# properjack.net
KiCad netlist of a schematic drawn in EAGLE
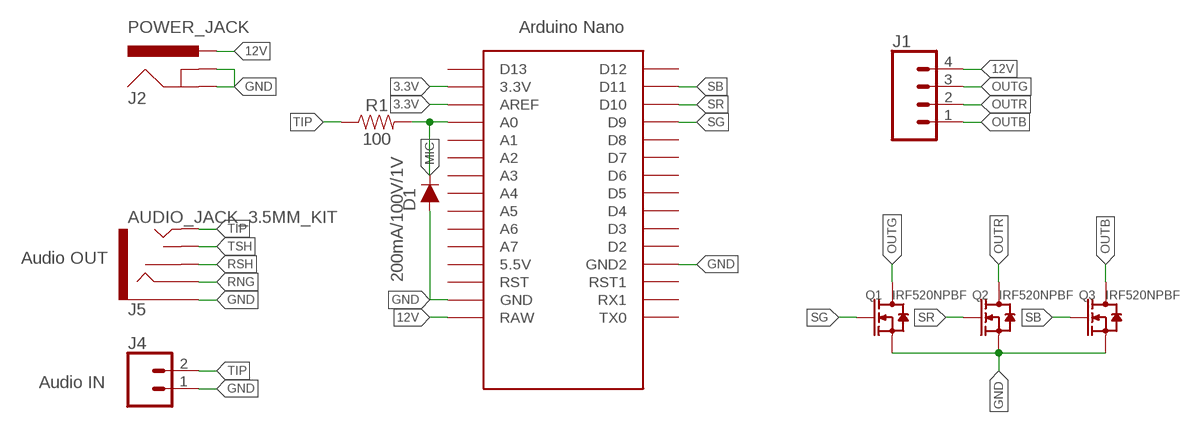
[diagram p0: schematic, sheet 1]

(export (version "E")
  (design (tool "Eeschema 10.0.6"))
  (components
    (comp (ref "D1")
      (value "200mA/100V/1V")
      (footprint "eagle-import:DIODE-1N4148")
      (libsource (lib "eagle-import") (part "DIODE-1N4148"))
    )
    (comp (ref "J1")
      (value "CONN_04LOCK_LONGPADS")
      (footprint "eagle-import:1X04_LOCK_LONGPADS")
      (libsource (lib "eagle-import") (part "CONN_04LOCK_LONGPADS"))
    )
    (comp (ref "J2")
      (value "POWER_JACK")
      (footprint "eagle-import:POWER_JACK_PTH")
      (libsource (lib "eagle-import") (part "POWER_JACK"))
    )
    (comp (ref "J4")
      (value "CONN_02LOCK_LONGPADS")
      (footprint "eagle-import:1X02_LOCK_LONGPADS")
      (libsource (lib "eagle-import") (part "CONN_02LOCK_LONGPADS"))
    )
    (comp (ref "J5")
      (value "AUDIO_JACK_3.5MM_KIT")
      (footprint "eagle-import:AUDIO-JACK-KIT")
      (libsource (lib "eagle-import") (part "AUDIO_JACK_3.5MM_KIT"))
    )
    (comp (ref "Q1")
      (value "IRF520NPBF")
      (footprint "eagle-import:TO-220")
      (libsource (lib "eagle-import") (part "DIP-MOSFET-N-CH-100V-9.7A-IRF520NPBF(TO-220AB)IRL2703"))
    )
    (comp (ref "Q2")
      (value "IRF520NPBF")
      (footprint "eagle-import:TO-220")
      (libsource (lib "eagle-import") (part "DIP-MOSFET-N-CH-100V-9.7A-IRF520NPBF(TO-220AB)IRL2703"))
    )
    (comp (ref "Q3")
      (value "IRF520NPBF")
      (footprint "eagle-import:TO-220")
      (libsource (lib "eagle-import") (part "DIP-MOSFET-N-CH-100V-9.7A-IRF520NPBF(TO-220AB)IRL2703"))
    )
    (comp (ref "R1")
      (value "100")
      (footprint "eagle-import:AXIAL-0.3")
      (libsource (lib "eagle-import") (part "100OHM-HORIZ-1/4W-1%"))
    )
    (comp (ref "U$1")
      (value "NANONOICSP")
      (footprint "eagle-import:NANO_2")
      (libsource (lib "eagle-import") (part "NANONOICSP"))
    )
  )
  (nets
    (net (code "1") (name "3.3V") (class "Default")
      (node (ref "U$1") (pin "3.3V") (pinfunction "3.3V_3.3V") (pintype "bidirectional"))
      (node (ref "U$1") (pin "AREF") (pinfunction "AREF_AREF") (pintype "bidirectional"))
    )
    (net (code "2") (name "12V") (class "Default")
      (node (ref "J1") (pin "4") (pinfunction "4_4") (pintype "passive"))
      (node (ref "J2") (pin "PWR") (pinfunction "PWR_PWR") (pintype "bidirectional"))
      (node (ref "U$1") (pin "RAW") (pinfunction "RAW_RAW") (pintype "bidirectional"))
    )
    (net (code "3") (name "GND") (class "Default")
      (node (ref "D1") (pin "A") (pinfunction "A_A") (pintype "passive"))
      (node (ref "J2") (pin "GND") (pinfunction "GND_GND") (pintype "bidirectional"))
      (node (ref "J2") (pin "GNDBREAK") (pinfunction "GNDBREAK_GNDBREAK") (pintype "bidirectional"))
      (node (ref "J4") (pin "1") (pinfunction "1_1") (pintype "passive"))
      (node (ref "J5") (pin "SLEEVE") (pinfunction "SLEEVE_SLEEVE") (pintype "bidirectional"))
      (node (ref "Q1") (pin "3") (pinfunction "S_3") (pintype "passive"))
      (node (ref "Q2") (pin "3") (pinfunction "S_3") (pintype "passive"))
      (node (ref "Q3") (pin "3") (pinfunction "S_3") (pintype "passive"))
      (node (ref "U$1") (pin "GND") (pinfunction "GND_GND") (pintype "bidirectional"))
      (node (ref "U$1") (pin "GND1") (pinfunction "GND2_GND1") (pintype "bidirectional"))
    )
    (net (code "4") (name "MIC") (class "Default")
      (node (ref "D1") (pin "C") (pinfunction "C_C") (pintype "passive"))
      (node (ref "R1") (pin "P$2") (pinfunction "2_P$2") (pintype "passive"))
      (node (ref "U$1") (pin "A0") (pinfunction "A0_A0") (pintype "bidirectional"))
    )
    (net (code "5") (name "OUTB") (class "Default")
      (node (ref "J1") (pin "1") (pinfunction "1_1") (pintype "passive"))
      (node (ref "Q3") (pin "2") (pinfunction "D_2") (pintype "passive"))
      (node (ref "Q3") (pin "HEAT") (pinfunction "D_HEAT") (pintype "passive"))
    )
    (net (code "6") (name "OUTG") (class "Default")
      (node (ref "J1") (pin "3") (pinfunction "3_3") (pintype "passive"))
      (node (ref "Q1") (pin "2") (pinfunction "D_2") (pintype "passive"))
      (node (ref "Q1") (pin "HEAT") (pinfunction "D_HEAT") (pintype "passive"))
    )
    (net (code "7") (name "OUTR") (class "Default")
      (node (ref "J1") (pin "2") (pinfunction "2_2") (pintype "passive"))
      (node (ref "Q2") (pin "2") (pinfunction "D_2") (pintype "passive"))
      (node (ref "Q2") (pin "HEAT") (pinfunction "D_HEAT") (pintype "passive"))
    )
    (net (code "8") (name "RNG") (class "Default")
      (node (ref "J5") (pin "RING") (pinfunction "RING_RING") (pintype "bidirectional"))
    )
    (net (code "9") (name "RSH") (class "Default")
      (node (ref "J5") (pin "RSH") (pinfunction "RSH_RSH") (pintype "bidirectional"))
    )
    (net (code "10") (name "SB") (class "Default")
      (node (ref "Q3") (pin "1") (pinfunction "G_1") (pintype "passive"))
      (node (ref "U$1") (pin "D11") (pinfunction "D11_D11") (pintype "bidirectional"))
    )
    (net (code "11") (name "SG") (class "Default")
      (node (ref "Q1") (pin "1") (pinfunction "G_1") (pintype "passive"))
      (node (ref "U$1") (pin "D9") (pinfunction "D9_D9") (pintype "bidirectional"))
    )
    (net (code "12") (name "SR") (class "Default")
      (node (ref "Q2") (pin "1") (pinfunction "G_1") (pintype "passive"))
      (node (ref "U$1") (pin "D10") (pinfunction "D10_D10") (pintype "bidirectional"))
    )
    (net (code "13") (name "TIP") (class "Default")
      (node (ref "J4") (pin "2") (pinfunction "2_2") (pintype "passive"))
      (node (ref "J5") (pin "TIP") (pinfunction "TIP_TIP") (pintype "bidirectional"))
      (node (ref "R1") (pin "P$1") (pinfunction "1_P$1") (pintype "passive"))
    )
    (net (code "14") (name "TSH") (class "Default")
      (node (ref "J5") (pin "TSH") (pinfunction "TSH_TSH") (pintype "bidirectional"))
    )
    (net (code "15") (name "unconnected-(U$1-5.5V-Pad5V)") (class "Default")
      (node (ref "U$1") (pin "5V") (pinfunction "5.5V_5V") (pintype "bidirectional"))
    )
    (net (code "16") (name "unconnected-(U$1-PadA1)") (class "Default")
      (node (ref "U$1") (pin "A1") (pinfunction "A1_A1") (pintype "bidirectional"))
    )
    (net (code "17") (name "unconnected-(U$1-PadA2)") (class "Default")
      (node (ref "U$1") (pin "A2") (pinfunction "A2_A2") (pintype "bidirectional"))
    )
    (net (code "18") (name "unconnected-(U$1-PadA3)") (class "Default")
      (node (ref "U$1") (pin "A3") (pinfunction "A3_A3") (pintype "bidirectional"))
    )
    (net (code "19") (name "unconnected-(U$1-PadA4)") (class "Default")
      (node (ref "U$1") (pin "A4") (pinfunction "A4_A4") (pintype "bidirectional"))
    )
    (net (code "20") (name "unconnected-(U$1-PadA5)") (class "Default")
      (node (ref "U$1") (pin "A5") (pinfunction "A5_A5") (pintype "bidirectional"))
    )
    (net (code "21") (name "unconnected-(U$1-PadA6)") (class "Default")
      (node (ref "U$1") (pin "A6") (pinfunction "A6_A6") (pintype "bidirectional"))
    )
    (net (code "22") (name "unconnected-(U$1-PadA7)") (class "Default")
      (node (ref "U$1") (pin "A7") (pinfunction "A7_A7") (pintype "bidirectional"))
    )
    (net (code "23") (name "unconnected-(U$1-PadD2)") (class "Default")
      (node (ref "U$1") (pin "D2") (pinfunction "D2_D2") (pintype "bidirectional"))
    )
    (net (code "24") (name "unconnected-(U$1-PadD3)") (class "Default")
      (node (ref "U$1") (pin "D3") (pinfunction "D3_D3") (pintype "bidirectional"))
    )
    (net (code "25") (name "unconnected-(U$1-PadD4)") (class "Default")
      (node (ref "U$1") (pin "D4") (pinfunction "D4_D4") (pintype "bidirectional"))
    )
    (net (code "26") (name "unconnected-(U$1-PadD5)") (class "Default")
      (node (ref "U$1") (pin "D5") (pinfunction "D5_D5") (pintype "bidirectional"))
    )
    (net (code "27") (name "unconnected-(U$1-PadD6)") (class "Default")
      (node (ref "U$1") (pin "D6") (pinfunction "D6_D6") (pintype "bidirectional"))
    )
    (net (code "28") (name "unconnected-(U$1-PadD7)") (class "Default")
      (node (ref "U$1") (pin "D7") (pinfunction "D7_D7") (pintype "bidirectional"))
    )
    (net (code "29") (name "unconnected-(U$1-PadD8)") (class "Default")
      (node (ref "U$1") (pin "D8") (pinfunction "D8_D8") (pintype "bidirectional"))
    )
    (net (code "30") (name "unconnected-(U$1-PadD12)") (class "Default")
      (node (ref "U$1") (pin "D12") (pinfunction "D12_D12") (pintype "bidirectional"))
    )
    (net (code "31") (name "unconnected-(U$1-PadD13)") (class "Default")
      (node (ref "U$1") (pin "D13") (pinfunction "D13_D13") (pintype "bidirectional"))
    )
    (net (code "32") (name "unconnected-(U$1-PadRST)") (class "Default")
      (node (ref "U$1") (pin "RST") (pinfunction "RST_RST") (pintype "bidirectional"))
    )
    (net (code "33") (name "unconnected-(U$1-PadRST1)") (class "Default")
      (node (ref "U$1") (pin "RST1") (pinfunction "RST1_RST1") (pintype "bidirectional"))
    )
    (net (code "34") (name "unconnected-(U$1-PadRX1)") (class "Default")
      (node (ref "U$1") (pin "RX1") (pinfunction "RX1_RX1") (pintype "bidirectional"))
    )
    (net (code "35") (name "unconnected-(U$1-PadTX0)") (class "Default")
      (node (ref "U$1") (pin "TX0") (pinfunction "TX0_TX0") (pintype "bidirectional"))
    )
  )
)
